# LNA.net
KiCad netlist of a schematic drawn in Altium Designer
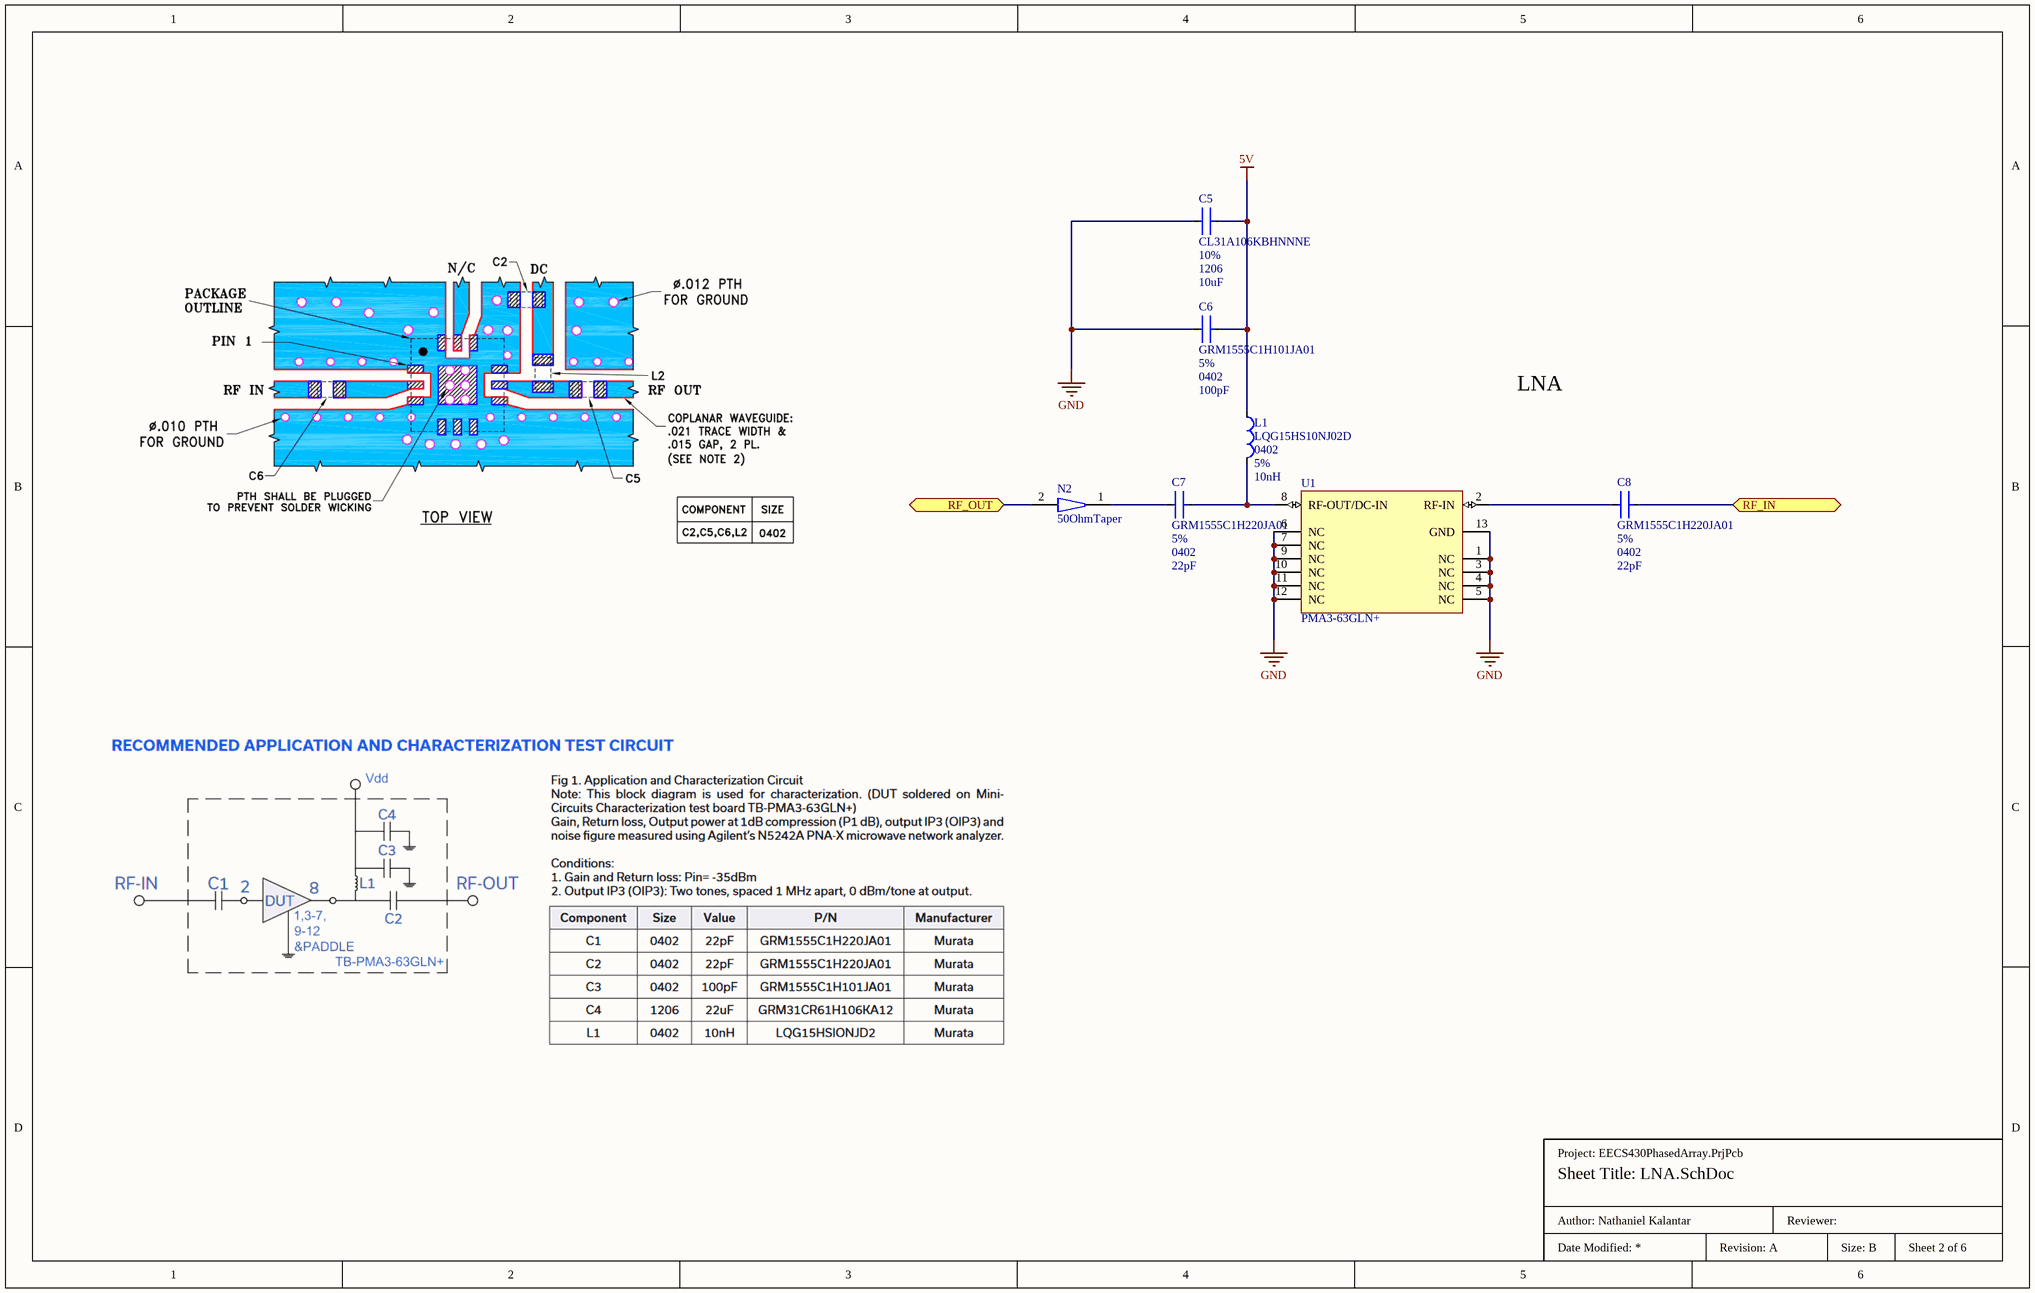
[diagram p0: LNA.SchDoc]

(export (version "E")
  (design (tool "Eeschema 10.0.6"))
  (components
    (comp (ref "C5")
      (value "CL31A106KBHNNNE")
      (footprint "Capactor1206_Samsung")
      (description "10 µF ±10% 50V Ceramic Capacitor X5R 1206 (3216 Metric)")
      (fields
        (field (name "TOLERANCE") "10%")
        (field (name "PACKAGE") "1206")
        (field (name "ALTIUM_VALUE") "10uF")
      )
      (libsource (lib "EECS430PhasedArray") (part "CL31A106KBHNNNE"))
    )
    (comp (ref "C6")
      (value "GRM1555C1H101JA01")
      (footprint "Capacitor0402_Murata")
      (description "100 pF ±5% 50V Ceramic Capacitor C0G, NP0 0402 (1005 Metric)")
      (fields
        (field (name "TOLERANCE") "5%")
        (field (name "PACKAGE") "0402")
        (field (name "ALTIUM_VALUE") "100pF")
      )
      (libsource (lib "EECS430PhasedArray") (part "GRM1555C1H101JA01"))
    )
    (comp (ref "C7")
      (value "GRM1555C1H220JA01")
      (footprint "Capacitor0402_Murata")
      (description "22 pF ±5% 50V Ceramic Capacitor C0G, NP0 0402 (1005 Metric)")
      (fields
        (field (name "TOLERANCE") "5%")
        (field (name "PACKAGE") "0402")
        (field (name "ALTIUM_VALUE") "22pF")
      )
      (libsource (lib "EECS430PhasedArray") (part "GRM1555C1H220JA01"))
    )
    (comp (ref "C8")
      (value "GRM1555C1H220JA01")
      (footprint "Capacitor0402_Murata")
      (description "22 pF ±5% 50V Ceramic Capacitor C0G, NP0 0402 (1005 Metric)")
      (fields
        (field (name "TOLERANCE") "5%")
        (field (name "PACKAGE") "0402")
        (field (name "ALTIUM_VALUE") "22pF")
      )
      (libsource (lib "EECS430PhasedArray") (part "GRM1555C1H220JA01"))
    )
    (comp (ref "L1")
      (value "LQG15HS10NJ02D")
      (footprint "FP-LQG15HH_02-IPC_B")
      (description "Multilayer type RF Inductor 10nH ±5% 0.26Ω 500mA 0402")
      (fields
        (field (name "CASE CODE (IMPERIAL)") "0402")
        (field (name "TOLERANCE") "5%")
        (field (name "INDUCTANCE") "10nH")
      )
      (libsource (lib "EECS430PhasedArray") (part "LQG15HS10NJ02D"))
    )
    (comp (ref "N2")
      (value "50OhmTaper")
      (footprint "50OhmTaper")
      (description "Triangular taper from 50 Ohms to 0402 width")
      (libsource (lib "EECS430PhasedArray") (part "50OhmTaper"))
    )
    (comp (ref "U1")
      (value "PMA3-63GLN+")
      (footprint "PMA3-63GLN+-QFN127P600-8N")
      (description "RF Amplifier IC LTE, Radar, SATCOM, UMTS, WiFi, WiMAX, WLAN 1.8GHz ~ 6GHz 12-MCLP (3x3)")
      (libsource (lib "EECS430PhasedArray") (part "PMA3-63GLN+"))
    )
  )
  (nets
    (net (code "1") (name "/RF_IN") (class "Default")
      (node (ref "C8") (pin "1") (pinfunction "1_1") (pintype "passive"))
    )
    (net (code "2") (name "/RF_OUT") (class "Default")
      (node (ref "N2") (pin "2") (pinfunction "2_2") (pintype "passive"))
    )
    (net (code "3") (name "5V") (class "Default")
      (node (ref "C5") (pin "1") (pinfunction "1_1") (pintype "passive"))
      (node (ref "C6") (pin "1") (pinfunction "1_1") (pintype "passive"))
      (node (ref "L1") (pin "2") (pinfunction "2_2") (pintype "passive"))
    )
    (net (code "4") (name "GND") (class "Default")
      (node (ref "C5") (pin "2") (pinfunction "2_2") (pintype "passive"))
      (node (ref "C6") (pin "2") (pinfunction "2_2") (pintype "passive"))
      (node (ref "U1") (pin "1") (pinfunction "NC_1") (pintype "passive"))
      (node (ref "U1") (pin "10") (pinfunction "NC_10") (pintype "passive"))
      (node (ref "U1") (pin "11") (pinfunction "NC_11") (pintype "passive"))
      (node (ref "U1") (pin "12") (pinfunction "NC_12") (pintype "passive"))
      (node (ref "U1") (pin "13") (pinfunction "GND_13") (pintype "power_in"))
      (node (ref "U1") (pin "3") (pinfunction "NC_3") (pintype "passive"))
      (node (ref "U1") (pin "4") (pinfunction "NC_4") (pintype "passive"))
      (node (ref "U1") (pin "5") (pinfunction "NC_5") (pintype "passive"))
      (node (ref "U1") (pin "6") (pinfunction "NC_6") (pintype "passive"))
      (node (ref "U1") (pin "7") (pinfunction "NC_7") (pintype "passive"))
      (node (ref "U1") (pin "9") (pinfunction "NC_9") (pintype "passive"))
    )
    (net (code "5") (name "Net-(C7-Pad2)") (class "Default")
      (node (ref "C7") (pin "2") (pinfunction "2_2") (pintype "passive"))
      (node (ref "N2") (pin "1") (pinfunction "1_1") (pintype "passive"))
    )
    (net (code "6") (name "Net-(U1-RF-IN)") (class "Default")
      (node (ref "C8") (pin "2") (pinfunction "2_2") (pintype "passive"))
      (node (ref "U1") (pin "2") (pinfunction "RF-IN_2") (pintype "bidirectional"))
    )
    (net (code "7") (name "Net-(U1-RF-OUT{slash}DC-IN)") (class "Default")
      (node (ref "C7") (pin "1") (pinfunction "1_1") (pintype "passive"))
      (node (ref "L1") (pin "1") (pinfunction "1_1") (pintype "passive"))
      (node (ref "U1") (pin "8") (pinfunction "RF-OUT/DC-IN_8") (pintype "bidirectional"))
    )
  )
)
